# PCB-BI8-2x4.net
KiCad netlist of a schematic drawn in EAGLE
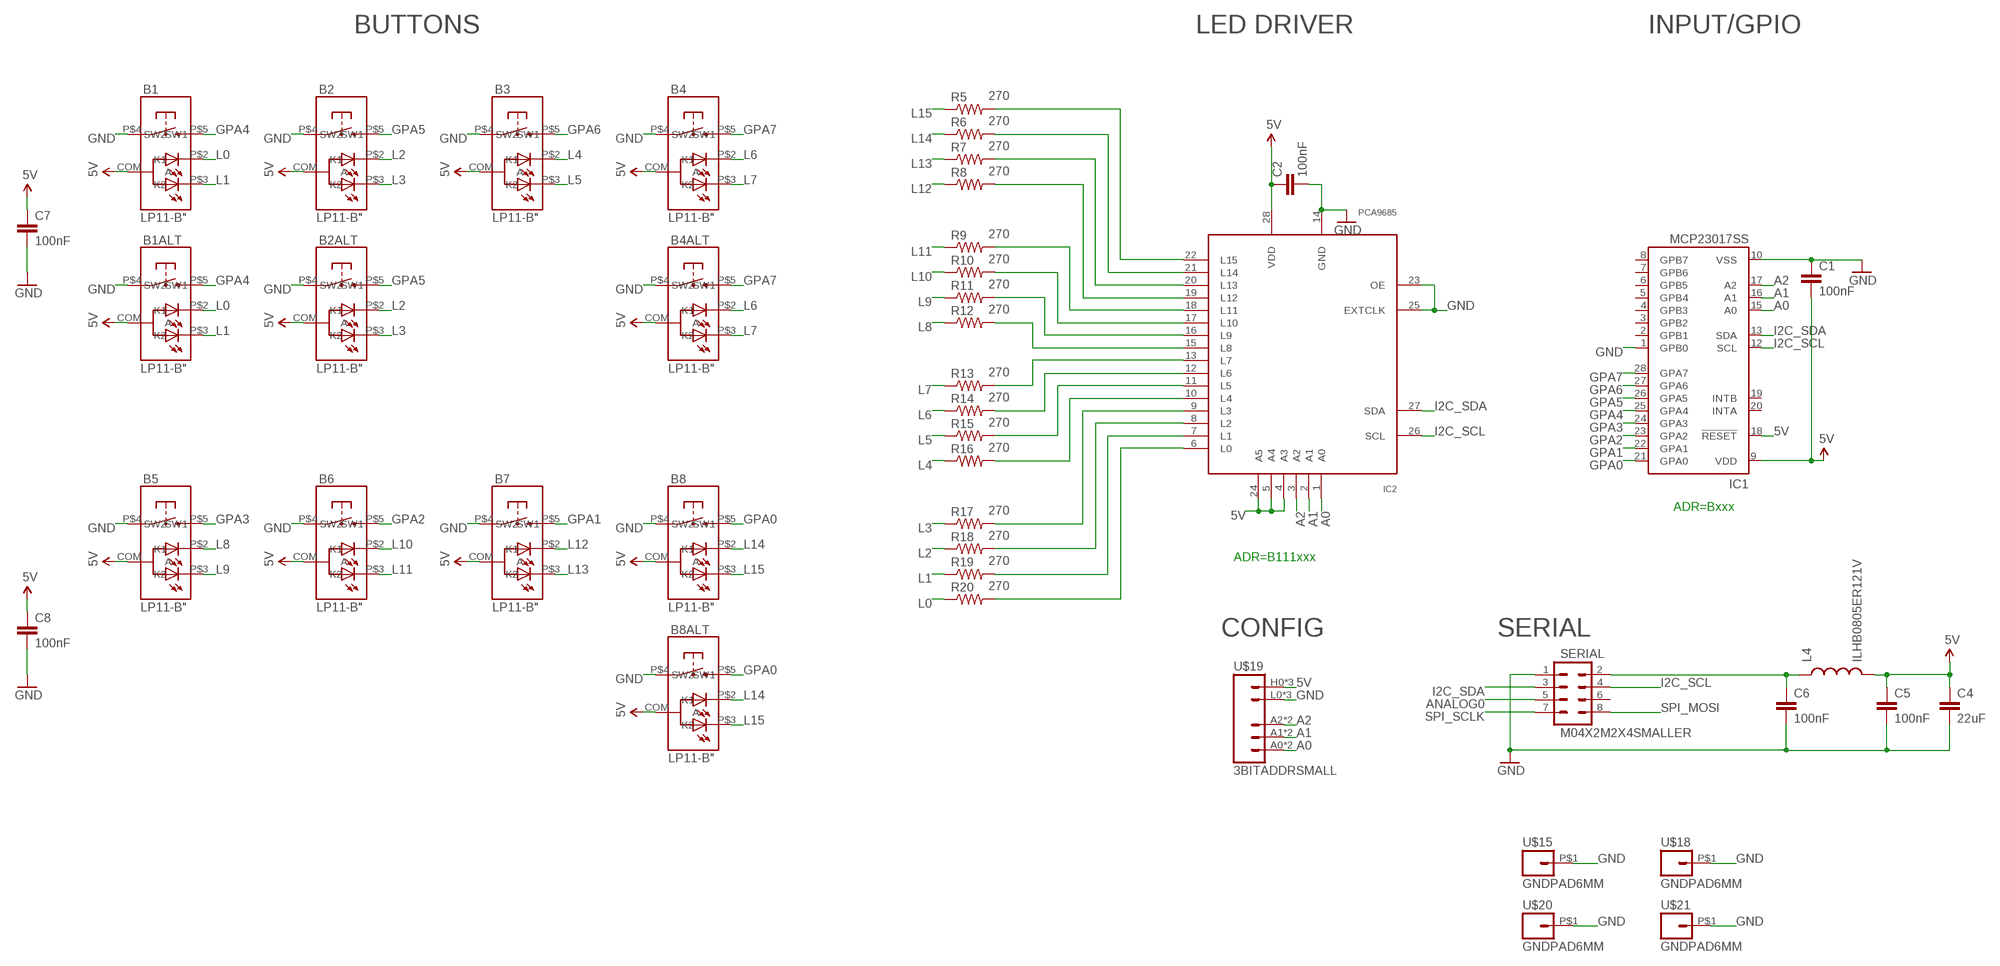
[diagram p0: schematic, sheet 1]

(export (version "E")
  (design (tool "Eeschema 10.0.6"))
  (components
    (comp (ref "B1")
      (value "LP11-B\"")
      (footprint "eagle-import:LP11")
      (libsource (lib "eagle-import") (part "LP11-B{dblquote}"))
    )
    (comp (ref "B1ALT")
      (value "LP11-B\"")
      (footprint "eagle-import:LP11")
      (libsource (lib "eagle-import") (part "LP11-B{dblquote}"))
    )
    (comp (ref "B2")
      (value "LP11-B\"")
      (footprint "eagle-import:LP11")
      (libsource (lib "eagle-import") (part "LP11-B{dblquote}"))
    )
    (comp (ref "B2ALT")
      (value "LP11-B\"")
      (footprint "eagle-import:LP11")
      (libsource (lib "eagle-import") (part "LP11-B{dblquote}"))
    )
    (comp (ref "B3")
      (value "LP11-B\"")
      (footprint "eagle-import:LP11")
      (libsource (lib "eagle-import") (part "LP11-B{dblquote}"))
    )
    (comp (ref "B4")
      (value "LP11-B\"")
      (footprint "eagle-import:LP11")
      (libsource (lib "eagle-import") (part "LP11-B{dblquote}"))
    )
    (comp (ref "B4ALT")
      (value "LP11-B\"")
      (footprint "eagle-import:LP11")
      (libsource (lib "eagle-import") (part "LP11-B{dblquote}"))
    )
    (comp (ref "B5")
      (value "LP11-B\"")
      (footprint "eagle-import:LP11")
      (libsource (lib "eagle-import") (part "LP11-B{dblquote}"))
    )
    (comp (ref "B6")
      (value "LP11-B\"")
      (footprint "eagle-import:LP11")
      (libsource (lib "eagle-import") (part "LP11-B{dblquote}"))
    )
    (comp (ref "B7")
      (value "LP11-B\"")
      (footprint "eagle-import:LP11")
      (libsource (lib "eagle-import") (part "LP11-B{dblquote}"))
    )
    (comp (ref "B8")
      (value "LP11-B\"")
      (footprint "eagle-import:LP11")
      (libsource (lib "eagle-import") (part "LP11-B{dblquote}"))
    )
    (comp (ref "B8ALT")
      (value "LP11-B\"")
      (footprint "eagle-import:LP11")
      (libsource (lib "eagle-import") (part "LP11-B{dblquote}"))
    )
    (comp (ref "C1")
      (value "100nF")
      (footprint "eagle-import:0603-CAP")
      (libsource (lib "eagle-import") (part "CAP0603-CAP"))
    )
    (comp (ref "C2")
      (value "100nF")
      (footprint "eagle-import:0603-CAP")
      (libsource (lib "eagle-import") (part "CAP0603-CAP"))
    )
    (comp (ref "C4")
      (value "22uF")
      (footprint "eagle-import:0805")
      (libsource (lib "eagle-import") (part "CAP0805"))
    )
    (comp (ref "C5")
      (value "100nF")
      (footprint "eagle-import:0603-CAP")
      (libsource (lib "eagle-import") (part "CAP0603-CAP"))
    )
    (comp (ref "C6")
      (value "100nF")
      (footprint "eagle-import:0603-CAP")
      (libsource (lib "eagle-import") (part "CAP0603-CAP"))
    )
    (comp (ref "C7")
      (value "100nF")
      (footprint "eagle-import:0603-CAP")
      (libsource (lib "eagle-import") (part "CAP0603-CAP"))
    )
    (comp (ref "C8")
      (value "100nF")
      (footprint "eagle-import:0603-CAP")
      (libsource (lib "eagle-import") (part "CAP0603-CAP"))
    )
    (comp (ref "IC1")
      (value "MCP23017SS")
      (footprint "eagle-import:SSOP28")
      (fields
        (field (name "MF") "MICROCHIP")
        (field (name "MPN") "MCP23017-E/SS")
        (field (name "MPN_1") "MCP23017-E/SS")
        (field (name "OC_FARNELL") "1467674")
        (field (name "OC_NEWARK") "31K2960")
      )
      (libsource (lib "eagle-import") (part "MCP23017SS"))
    )
    (comp (ref "IC2")
      (value "PCA9685")
      (footprint "eagle-import:TSSOP28")
      (libsource (lib "eagle-import") (part "PCA9685"))
    )
    (comp (ref "L4")
      (value "ILHB0805ER121V")
      (footprint "eagle-import:0805")
      (libsource (lib "eagle-import") (part "INDUCTOR0805"))
    )
    (comp (ref "R5")
      (value "270")
      (footprint "eagle-import:0603-RES")
      (libsource (lib "eagle-import") (part "RESISTOR0603-RES"))
    )
    (comp (ref "R6")
      (value "270")
      (footprint "eagle-import:0603-RES")
      (libsource (lib "eagle-import") (part "RESISTOR0603-RES"))
    )
    (comp (ref "R7")
      (value "270")
      (footprint "eagle-import:0603-RES")
      (libsource (lib "eagle-import") (part "RESISTOR0603-RES"))
    )
    (comp (ref "R8")
      (value "270")
      (footprint "eagle-import:0603-RES")
      (libsource (lib "eagle-import") (part "RESISTOR0603-RES"))
    )
    (comp (ref "R9")
      (value "270")
      (footprint "eagle-import:0603-RES")
      (libsource (lib "eagle-import") (part "RESISTOR0603-RES"))
    )
    (comp (ref "R10")
      (value "270")
      (footprint "eagle-import:0603-RES")
      (libsource (lib "eagle-import") (part "RESISTOR0603-RES"))
    )
    (comp (ref "R11")
      (value "270")
      (footprint "eagle-import:0603-RES")
      (libsource (lib "eagle-import") (part "RESISTOR0603-RES"))
    )
    (comp (ref "R12")
      (value "270")
      (footprint "eagle-import:0603-RES")
      (libsource (lib "eagle-import") (part "RESISTOR0603-RES"))
    )
    (comp (ref "R13")
      (value "270")
      (footprint "eagle-import:0603-RES")
      (libsource (lib "eagle-import") (part "RESISTOR0603-RES"))
    )
    (comp (ref "R14")
      (value "270")
      (footprint "eagle-import:0603-RES")
      (libsource (lib "eagle-import") (part "RESISTOR0603-RES"))
    )
    (comp (ref "R15")
      (value "270")
      (footprint "eagle-import:0603-RES")
      (libsource (lib "eagle-import") (part "RESISTOR0603-RES"))
    )
    (comp (ref "R16")
      (value "270")
      (footprint "eagle-import:0603-RES")
      (libsource (lib "eagle-import") (part "RESISTOR0603-RES"))
    )
    (comp (ref "R17")
      (value "270")
      (footprint "eagle-import:0603-RES")
      (libsource (lib "eagle-import") (part "RESISTOR0603-RES"))
    )
    (comp (ref "R18")
      (value "270")
      (footprint "eagle-import:0603-RES")
      (libsource (lib "eagle-import") (part "RESISTOR0603-RES"))
    )
    (comp (ref "R19")
      (value "270")
      (footprint "eagle-import:0603-RES")
      (libsource (lib "eagle-import") (part "RESISTOR0603-RES"))
    )
    (comp (ref "R20")
      (value "270")
      (footprint "eagle-import:0603-RES")
      (libsource (lib "eagle-import") (part "RESISTOR0603-RES"))
    )
    (comp (ref "SERIAL")
      (value "M04X2M2X4SMALLER")
      (footprint "eagle-import:M2X4SMALLER")
      (libsource (lib "eagle-import") (part "M04X2M2X4SMALLER"))
    )
    (comp (ref "U$15")
      (value "GNDPAD6MM")
      (footprint "eagle-import:3.2MMPAD6MM")
      (libsource (lib "eagle-import") (part "GNDPAD6MM"))
    )
    (comp (ref "U$18")
      (value "GNDPAD6MM")
      (footprint "eagle-import:3.2MMPAD6MM")
      (libsource (lib "eagle-import") (part "GNDPAD6MM"))
    )
    (comp (ref "U$19")
      (value "3BITADDRSMALL")
      (footprint "eagle-import:3BITADDR_SMALL")
      (libsource (lib "eagle-import") (part "3BITADDRSMALL"))
    )
    (comp (ref "U$20")
      (value "GNDPAD6MM")
      (footprint "eagle-import:3.2MMPAD6MM")
      (libsource (lib "eagle-import") (part "GNDPAD6MM"))
    )
    (comp (ref "U$21")
      (value "GNDPAD6MM")
      (footprint "eagle-import:3.2MMPAD6MM")
      (libsource (lib "eagle-import") (part "GNDPAD6MM"))
    )
  )
  (nets
    (net (code "1") (name "5V") (class "Default")
      (node (ref "B1") (pin "COM") (pinfunction "A_COM") (pintype "bidirectional"))
      (node (ref "B1ALT") (pin "COM") (pinfunction "A_COM") (pintype "bidirectional"))
      (node (ref "B2") (pin "COM") (pinfunction "A_COM") (pintype "bidirectional"))
      (node (ref "B2ALT") (pin "COM") (pinfunction "A_COM") (pintype "bidirectional"))
      (node (ref "B3") (pin "COM") (pinfunction "A_COM") (pintype "bidirectional"))
      (node (ref "B4") (pin "COM") (pinfunction "A_COM") (pintype "bidirectional"))
      (node (ref "B4ALT") (pin "COM") (pinfunction "A_COM") (pintype "bidirectional"))
      (node (ref "B5") (pin "COM") (pinfunction "A_COM") (pintype "bidirectional"))
      (node (ref "B6") (pin "COM") (pinfunction "A_COM") (pintype "bidirectional"))
      (node (ref "B7") (pin "COM") (pinfunction "A_COM") (pintype "bidirectional"))
      (node (ref "B8") (pin "COM") (pinfunction "A_COM") (pintype "bidirectional"))
      (node (ref "B8ALT") (pin "COM") (pinfunction "A_COM") (pintype "bidirectional"))
      (node (ref "C1") (pin "2") (pinfunction "2_2") (pintype "passive"))
      (node (ref "C2") (pin "1") (pinfunction "1_1") (pintype "passive"))
      (node (ref "C4") (pin "1") (pinfunction "1_1") (pintype "passive"))
      (node (ref "C5") (pin "1") (pinfunction "1_1") (pintype "passive"))
      (node (ref "C7") (pin "1") (pinfunction "1_1") (pintype "passive"))
      (node (ref "C8") (pin "1") (pinfunction "1_1") (pintype "passive"))
      (node (ref "IC1") (pin "18") (pinfunction "~{RESET}_18") (pintype "input"))
      (node (ref "IC1") (pin "9") (pinfunction "VDD_9") (pintype "power_in"))
      (node (ref "IC2") (pin "24") (pinfunction "A5_24") (pintype "input"))
      (node (ref "IC2") (pin "28") (pinfunction "VDD_28") (pintype "power_in"))
      (node (ref "IC2") (pin "4") (pinfunction "A3_4") (pintype "input"))
      (node (ref "IC2") (pin "5") (pinfunction "A4_5") (pintype "input"))
      (node (ref "L4") (pin "2") (pinfunction "2_2") (pintype "passive"))
      (node (ref "U$19") (pin "H0") (pinfunction "VCC_H0") (pintype "passive"))
      (node (ref "U$19") (pin "H1") (pinfunction "VCC_H1") (pintype "passive"))
      (node (ref "U$19") (pin "H2") (pinfunction "VCC_H2") (pintype "passive"))
    )
    (net (code "2") (name "A0") (class "Default")
      (node (ref "IC1") (pin "15") (pinfunction "A0_15") (pintype "input"))
      (node (ref "IC2") (pin "1") (pinfunction "A0_1") (pintype "input"))
      (node (ref "U$19") (pin "A0") (pinfunction "A0_A0") (pintype "passive"))
      (node (ref "U$19") (pin "AS0") (pinfunction "A0_AS0") (pintype "passive"))
    )
    (net (code "3") (name "A1") (class "Default")
      (node (ref "IC1") (pin "16") (pinfunction "A1_16") (pintype "input"))
      (node (ref "IC2") (pin "2") (pinfunction "A1_2") (pintype "input"))
      (node (ref "U$19") (pin "A1") (pinfunction "A1_A1") (pintype "passive"))
      (node (ref "U$19") (pin "AS1") (pinfunction "A1_AS1") (pintype "passive"))
    )
    (net (code "4") (name "A2") (class "Default")
      (node (ref "IC1") (pin "17") (pinfunction "A2_17") (pintype "input"))
      (node (ref "IC2") (pin "3") (pinfunction "A2_3") (pintype "input"))
      (node (ref "U$19") (pin "A2") (pinfunction "A2_A2") (pintype "passive"))
      (node (ref "U$19") (pin "AS2") (pinfunction "A2_AS2") (pintype "passive"))
    )
    (net (code "5") (name "ANALOG0") (class "Default")
      (node (ref "SERIAL") (pin "5") (pinfunction "5_5") (pintype "passive"))
    )
    (net (code "6") (name "GND") (class "Default")
      (node (ref "B1") (pin "P$4") (pinfunction "SW1_P$4") (pintype "bidirectional"))
      (node (ref "B1ALT") (pin "P$4") (pinfunction "SW1_P$4") (pintype "bidirectional"))
      (node (ref "B2") (pin "P$4") (pinfunction "SW1_P$4") (pintype "bidirectional"))
      (node (ref "B2ALT") (pin "P$4") (pinfunction "SW1_P$4") (pintype "bidirectional"))
      (node (ref "B3") (pin "P$4") (pinfunction "SW1_P$4") (pintype "bidirectional"))
      (node (ref "B4") (pin "P$4") (pinfunction "SW1_P$4") (pintype "bidirectional"))
      (node (ref "B4ALT") (pin "P$4") (pinfunction "SW1_P$4") (pintype "bidirectional"))
      (node (ref "B5") (pin "P$4") (pinfunction "SW1_P$4") (pintype "bidirectional"))
      (node (ref "B6") (pin "P$4") (pinfunction "SW1_P$4") (pintype "bidirectional"))
      (node (ref "B7") (pin "P$4") (pinfunction "SW1_P$4") (pintype "bidirectional"))
      (node (ref "B8") (pin "P$4") (pinfunction "SW1_P$4") (pintype "bidirectional"))
      (node (ref "B8ALT") (pin "P$4") (pinfunction "SW1_P$4") (pintype "bidirectional"))
      (node (ref "C1") (pin "1") (pinfunction "1_1") (pintype "passive"))
      (node (ref "C2") (pin "2") (pinfunction "2_2") (pintype "passive"))
      (node (ref "C4") (pin "2") (pinfunction "2_2") (pintype "passive"))
      (node (ref "C5") (pin "2") (pinfunction "2_2") (pintype "passive"))
      (node (ref "C6") (pin "2") (pinfunction "2_2") (pintype "passive"))
      (node (ref "C7") (pin "2") (pinfunction "2_2") (pintype "passive"))
      (node (ref "C8") (pin "2") (pinfunction "2_2") (pintype "passive"))
      (node (ref "IC1") (pin "1") (pinfunction "GPB0_1") (pintype "bidirectional"))
      (node (ref "IC1") (pin "10") (pinfunction "VSS_10") (pintype "power_in"))
      (node (ref "IC2") (pin "14") (pinfunction "GND_14") (pintype "power_in"))
      (node (ref "IC2") (pin "23") (pinfunction "OE_23") (pintype "input"))
      (node (ref "IC2") (pin "25") (pinfunction "EXTCLK_25") (pintype "input"))
      (node (ref "SERIAL") (pin "1") (pinfunction "1_1") (pintype "passive"))
      (node (ref "U$15") (pin "P$1") (pinfunction "1_P$1") (pintype "passive"))
      (node (ref "U$18") (pin "P$1") (pinfunction "1_P$1") (pintype "passive"))
      (node (ref "U$19") (pin "L0") (pinfunction "GND_L0") (pintype "passive"))
      (node (ref "U$19") (pin "L1") (pinfunction "GND_L1") (pintype "passive"))
      (node (ref "U$19") (pin "L2") (pinfunction "GND_L2") (pintype "passive"))
      (node (ref "U$20") (pin "P$1") (pinfunction "1_P$1") (pintype "passive"))
      (node (ref "U$21") (pin "P$1") (pinfunction "1_P$1") (pintype "passive"))
    )
    (net (code "7") (name "GPA0") (class "Default")
      (node (ref "B8") (pin "P$5") (pinfunction "SW2_P$5") (pintype "bidirectional"))
      (node (ref "B8ALT") (pin "P$5") (pinfunction "SW2_P$5") (pintype "bidirectional"))
      (node (ref "IC1") (pin "21") (pinfunction "GPA0_21") (pintype "bidirectional"))
    )
    (net (code "8") (name "GPA1") (class "Default")
      (node (ref "B7") (pin "P$5") (pinfunction "SW2_P$5") (pintype "bidirectional"))
      (node (ref "IC1") (pin "22") (pinfunction "GPA1_22") (pintype "bidirectional"))
    )
    (net (code "9") (name "GPA2") (class "Default")
      (node (ref "B6") (pin "P$5") (pinfunction "SW2_P$5") (pintype "bidirectional"))
      (node (ref "IC1") (pin "23") (pinfunction "GPA2_23") (pintype "bidirectional"))
    )
    (net (code "10") (name "GPA3") (class "Default")
      (node (ref "B5") (pin "P$5") (pinfunction "SW2_P$5") (pintype "bidirectional"))
      (node (ref "IC1") (pin "24") (pinfunction "GPA3_24") (pintype "bidirectional"))
    )
    (net (code "11") (name "GPA4") (class "Default")
      (node (ref "B1") (pin "P$5") (pinfunction "SW2_P$5") (pintype "bidirectional"))
      (node (ref "B1ALT") (pin "P$5") (pinfunction "SW2_P$5") (pintype "bidirectional"))
      (node (ref "IC1") (pin "25") (pinfunction "GPA4_25") (pintype "bidirectional"))
    )
    (net (code "12") (name "GPA5") (class "Default")
      (node (ref "B2") (pin "P$5") (pinfunction "SW2_P$5") (pintype "bidirectional"))
      (node (ref "B2ALT") (pin "P$5") (pinfunction "SW2_P$5") (pintype "bidirectional"))
      (node (ref "IC1") (pin "26") (pinfunction "GPA5_26") (pintype "bidirectional"))
    )
    (net (code "13") (name "GPA6") (class "Default")
      (node (ref "B3") (pin "P$5") (pinfunction "SW2_P$5") (pintype "bidirectional"))
      (node (ref "IC1") (pin "27") (pinfunction "GPA6_27") (pintype "bidirectional"))
    )
    (net (code "14") (name "GPA7") (class "Default")
      (node (ref "B4") (pin "P$5") (pinfunction "SW2_P$5") (pintype "bidirectional"))
      (node (ref "B4ALT") (pin "P$5") (pinfunction "SW2_P$5") (pintype "bidirectional"))
      (node (ref "IC1") (pin "28") (pinfunction "GPA7_28") (pintype "bidirectional"))
    )
    (net (code "15") (name "I2C_SCL") (class "Default")
      (node (ref "IC1") (pin "12") (pinfunction "SCL_12") (pintype "input"))
      (node (ref "IC2") (pin "26") (pinfunction "SCL_26") (pintype "input"))
      (node (ref "SERIAL") (pin "4") (pinfunction "4_4") (pintype "passive"))
    )
    (net (code "16") (name "I2C_SDA") (class "Default")
      (node (ref "IC1") (pin "13") (pinfunction "SDA_13") (pintype "bidirectional"))
      (node (ref "IC2") (pin "27") (pinfunction "SDA_27") (pintype "input"))
      (node (ref "SERIAL") (pin "3") (pinfunction "3_3") (pintype "passive"))
    )
    (net (code "17") (name "L0") (class "Default")
      (node (ref "B1") (pin "P$2") (pinfunction "K1_P$2") (pintype "bidirectional"))
      (node (ref "B1ALT") (pin "P$2") (pinfunction "K1_P$2") (pintype "bidirectional"))
      (node (ref "R20") (pin "1") (pinfunction "1_1") (pintype "passive"))
    )
    (net (code "18") (name "L1") (class "Default")
      (node (ref "B1") (pin "P$3") (pinfunction "K2_P$3") (pintype "bidirectional"))
      (node (ref "B1ALT") (pin "P$3") (pinfunction "K2_P$3") (pintype "bidirectional"))
      (node (ref "R19") (pin "1") (pinfunction "1_1") (pintype "passive"))
    )
    (net (code "19") (name "L2") (class "Default")
      (node (ref "B2") (pin "P$2") (pinfunction "K1_P$2") (pintype "bidirectional"))
      (node (ref "B2ALT") (pin "P$2") (pinfunction "K1_P$2") (pintype "bidirectional"))
      (node (ref "R18") (pin "1") (pinfunction "1_1") (pintype "passive"))
    )
    (net (code "20") (name "L3") (class "Default")
      (node (ref "B2") (pin "P$3") (pinfunction "K2_P$3") (pintype "bidirectional"))
      (node (ref "B2ALT") (pin "P$3") (pinfunction "K2_P$3") (pintype "bidirectional"))
      (node (ref "R17") (pin "1") (pinfunction "1_1") (pintype "passive"))
    )
    (net (code "21") (name "L4") (class "Default")
      (node (ref "B3") (pin "P$2") (pinfunction "K1_P$2") (pintype "bidirectional"))
      (node (ref "R16") (pin "1") (pinfunction "1_1") (pintype "passive"))
    )
    (net (code "22") (name "L5") (class "Default")
      (node (ref "B3") (pin "P$3") (pinfunction "K2_P$3") (pintype "bidirectional"))
      (node (ref "R15") (pin "1") (pinfunction "1_1") (pintype "passive"))
    )
    (net (code "23") (name "L6") (class "Default")
      (node (ref "B4") (pin "P$2") (pinfunction "K1_P$2") (pintype "bidirectional"))
      (node (ref "B4ALT") (pin "P$2") (pinfunction "K1_P$2") (pintype "bidirectional"))
      (node (ref "R14") (pin "1") (pinfunction "1_1") (pintype "passive"))
    )
    (net (code "24") (name "L7") (class "Default")
      (node (ref "B4") (pin "P$3") (pinfunction "K2_P$3") (pintype "bidirectional"))
      (node (ref "B4ALT") (pin "P$3") (pinfunction "K2_P$3") (pintype "bidirectional"))
      (node (ref "R13") (pin "1") (pinfunction "1_1") (pintype "passive"))
    )
    (net (code "25") (name "L8") (class "Default")
      (node (ref "B5") (pin "P$2") (pinfunction "K1_P$2") (pintype "bidirectional"))
      (node (ref "R12") (pin "1") (pinfunction "1_1") (pintype "passive"))
    )
    (net (code "26") (name "L9") (class "Default")
      (node (ref "B5") (pin "P$3") (pinfunction "K2_P$3") (pintype "bidirectional"))
      (node (ref "R11") (pin "1") (pinfunction "1_1") (pintype "passive"))
    )
    (net (code "27") (name "L10") (class "Default")
      (node (ref "B6") (pin "P$2") (pinfunction "K1_P$2") (pintype "bidirectional"))
      (node (ref "R10") (pin "1") (pinfunction "1_1") (pintype "passive"))
    )
    (net (code "28") (name "L11") (class "Default")
      (node (ref "B6") (pin "P$3") (pinfunction "K2_P$3") (pintype "bidirectional"))
      (node (ref "R9") (pin "1") (pinfunction "1_1") (pintype "passive"))
    )
    (net (code "29") (name "L12") (class "Default")
      (node (ref "B7") (pin "P$2") (pinfunction "K1_P$2") (pintype "bidirectional"))
      (node (ref "R8") (pin "1") (pinfunction "1_1") (pintype "passive"))
    )
    (net (code "30") (name "L13") (class "Default")
      (node (ref "B7") (pin "P$3") (pinfunction "K2_P$3") (pintype "bidirectional"))
      (node (ref "R7") (pin "1") (pinfunction "1_1") (pintype "passive"))
    )
    (net (code "31") (name "L14") (class "Default")
      (node (ref "B8") (pin "P$2") (pinfunction "K1_P$2") (pintype "bidirectional"))
      (node (ref "B8ALT") (pin "P$2") (pinfunction "K1_P$2") (pintype "bidirectional"))
      (node (ref "R6") (pin "1") (pinfunction "1_1") (pintype "passive"))
    )
    (net (code "32") (name "L15") (class "Default")
      (node (ref "B8") (pin "P$3") (pinfunction "K2_P$3") (pintype "bidirectional"))
      (node (ref "B8ALT") (pin "P$3") (pinfunction "K2_P$3") (pintype "bidirectional"))
      (node (ref "R5") (pin "1") (pinfunction "1_1") (pintype "passive"))
    )
    (net (code "33") (name "Net-(C6-Pad1)") (class "Default")
      (node (ref "C6") (pin "1") (pinfunction "1_1") (pintype "passive"))
      (node (ref "L4") (pin "1") (pinfunction "1_1") (pintype "passive"))
      (node (ref "SERIAL") (pin "2") (pinfunction "2_2") (pintype "passive"))
    )
    (net (code "34") (name "Net-(IC2-L0)") (class "Default")
      (node (ref "IC2") (pin "6") (pinfunction "L0_6") (pintype "output"))
      (node (ref "R20") (pin "2") (pinfunction "2_2") (pintype "passive"))
    )
    (net (code "35") (name "Net-(IC2-L1)") (class "Default")
      (node (ref "IC2") (pin "7") (pinfunction "L1_7") (pintype "output"))
      (node (ref "R19") (pin "2") (pinfunction "2_2") (pintype "passive"))
    )
    (net (code "36") (name "Net-(IC2-L2)") (class "Default")
      (node (ref "IC2") (pin "8") (pinfunction "L2_8") (pintype "output"))
      (node (ref "R18") (pin "2") (pinfunction "2_2") (pintype "passive"))
    )
    (net (code "37") (name "Net-(IC2-L3)") (class "Default")
      (node (ref "IC2") (pin "9") (pinfunction "L3_9") (pintype "output"))
      (node (ref "R17") (pin "2") (pinfunction "2_2") (pintype "passive"))
    )
    (net (code "38") (name "Net-(IC2-L4)") (class "Default")
      (node (ref "IC2") (pin "10") (pinfunction "L4_10") (pintype "output"))
      (node (ref "R16") (pin "2") (pinfunction "2_2") (pintype "passive"))
    )
    (net (code "39") (name "Net-(IC2-L5)") (class "Default")
      (node (ref "IC2") (pin "11") (pinfunction "L5_11") (pintype "output"))
      (node (ref "R15") (pin "2") (pinfunction "2_2") (pintype "passive"))
    )
    (net (code "40") (name "Net-(IC2-L6)") (class "Default")
      (node (ref "IC2") (pin "12") (pinfunction "L6_12") (pintype "output"))
      (node (ref "R14") (pin "2") (pinfunction "2_2") (pintype "passive"))
    )
    (net (code "41") (name "Net-(IC2-L7)") (class "Default")
      (node (ref "IC2") (pin "13") (pinfunction "L7_13") (pintype "output"))
      (node (ref "R13") (pin "2") (pinfunction "2_2") (pintype "passive"))
    )
    (net (code "42") (name "Net-(IC2-L8)") (class "Default")
      (node (ref "IC2") (pin "15") (pinfunction "L8_15") (pintype "output"))
      (node (ref "R12") (pin "2") (pinfunction "2_2") (pintype "passive"))
    )
    (net (code "43") (name "Net-(IC2-L9)") (class "Default")
      (node (ref "IC2") (pin "16") (pinfunction "L9_16") (pintype "output"))
      (node (ref "R11") (pin "2") (pinfunction "2_2") (pintype "passive"))
    )
    (net (code "44") (name "Net-(IC2-L10)") (class "Default")
      (node (ref "IC2") (pin "17") (pinfunction "L10_17") (pintype "output"))
      (node (ref "R10") (pin "2") (pinfunction "2_2") (pintype "passive"))
    )
    (net (code "45") (name "Net-(IC2-L11)") (class "Default")
      (node (ref "IC2") (pin "18") (pinfunction "L11_18") (pintype "output"))
      (node (ref "R9") (pin "2") (pinfunction "2_2") (pintype "passive"))
    )
    (net (code "46") (name "Net-(IC2-L12)") (class "Default")
      (node (ref "IC2") (pin "19") (pinfunction "L12_19") (pintype "output"))
      (node (ref "R8") (pin "2") (pinfunction "2_2") (pintype "passive"))
    )
    (net (code "47") (name "Net-(IC2-L13)") (class "Default")
      (node (ref "IC2") (pin "20") (pinfunction "L13_20") (pintype "output"))
      (node (ref "R7") (pin "2") (pinfunction "2_2") (pintype "passive"))
    )
    (net (code "48") (name "Net-(IC2-L14)") (class "Default")
      (node (ref "IC2") (pin "21") (pinfunction "L14_21") (pintype "output"))
      (node (ref "R6") (pin "2") (pinfunction "2_2") (pintype "passive"))
    )
    (net (code "49") (name "Net-(IC2-L15)") (class "Default")
      (node (ref "IC2") (pin "22") (pinfunction "L15_22") (pintype "output"))
      (node (ref "R5") (pin "2") (pinfunction "2_2") (pintype "passive"))
    )
    (net (code "50") (name "SPI_MOSI") (class "Default")
      (node (ref "SERIAL") (pin "8") (pinfunction "8_8") (pintype "passive"))
    )
    (net (code "51") (name "SPI_SCLK") (class "Default")
      (node (ref "SERIAL") (pin "7") (pinfunction "7_7") (pintype "passive"))
    )
    (net (code "52") (name "unconnected-(IC1-GPB1-Pad2)") (class "Default")
      (node (ref "IC1") (pin "2") (pinfunction "GPB1_2") (pintype "bidirectional"))
    )
    (net (code "53") (name "unconnected-(IC1-GPB2-Pad3)") (class "Default")
      (node (ref "IC1") (pin "3") (pinfunction "GPB2_3") (pintype "bidirectional"))
    )
    (net (code "54") (name "unconnected-(IC1-GPB3-Pad4)") (class "Default")
      (node (ref "IC1") (pin "4") (pinfunction "GPB3_4") (pintype "bidirectional"))
    )
    (net (code "55") (name "unconnected-(IC1-GPB4-Pad5)") (class "Default")
      (node (ref "IC1") (pin "5") (pinfunction "GPB4_5") (pintype "bidirectional"))
    )
    (net (code "56") (name "unconnected-(IC1-GPB5-Pad6)") (class "Default")
      (node (ref "IC1") (pin "6") (pinfunction "GPB5_6") (pintype "bidirectional"))
    )
    (net (code "57") (name "unconnected-(IC1-GPB6-Pad7)") (class "Default")
      (node (ref "IC1") (pin "7") (pinfunction "GPB6_7") (pintype "bidirectional"))
    )
    (net (code "58") (name "unconnected-(IC1-GPB7-Pad8)") (class "Default")
      (node (ref "IC1") (pin "8") (pinfunction "GPB7_8") (pintype "bidirectional"))
    )
    (net (code "59") (name "unconnected-(IC1-INTA-Pad20)") (class "Default")
      (node (ref "IC1") (pin "20") (pinfunction "INTA_20") (pintype "output"))
    )
    (net (code "60") (name "unconnected-(IC1-INTB-Pad19)") (class "Default")
      (node (ref "IC1") (pin "19") (pinfunction "INTB_19") (pintype "output"))
    )
    (net (code "61") (name "unconnected-(SERIAL-Pad6)") (class "Default")
      (node (ref "SERIAL") (pin "6") (pinfunction "6_6") (pintype "passive"))
    )
  )
)
